# fasciaMainBoard_V0.net
KiCad netlist of a schematic drawn in EAGLE
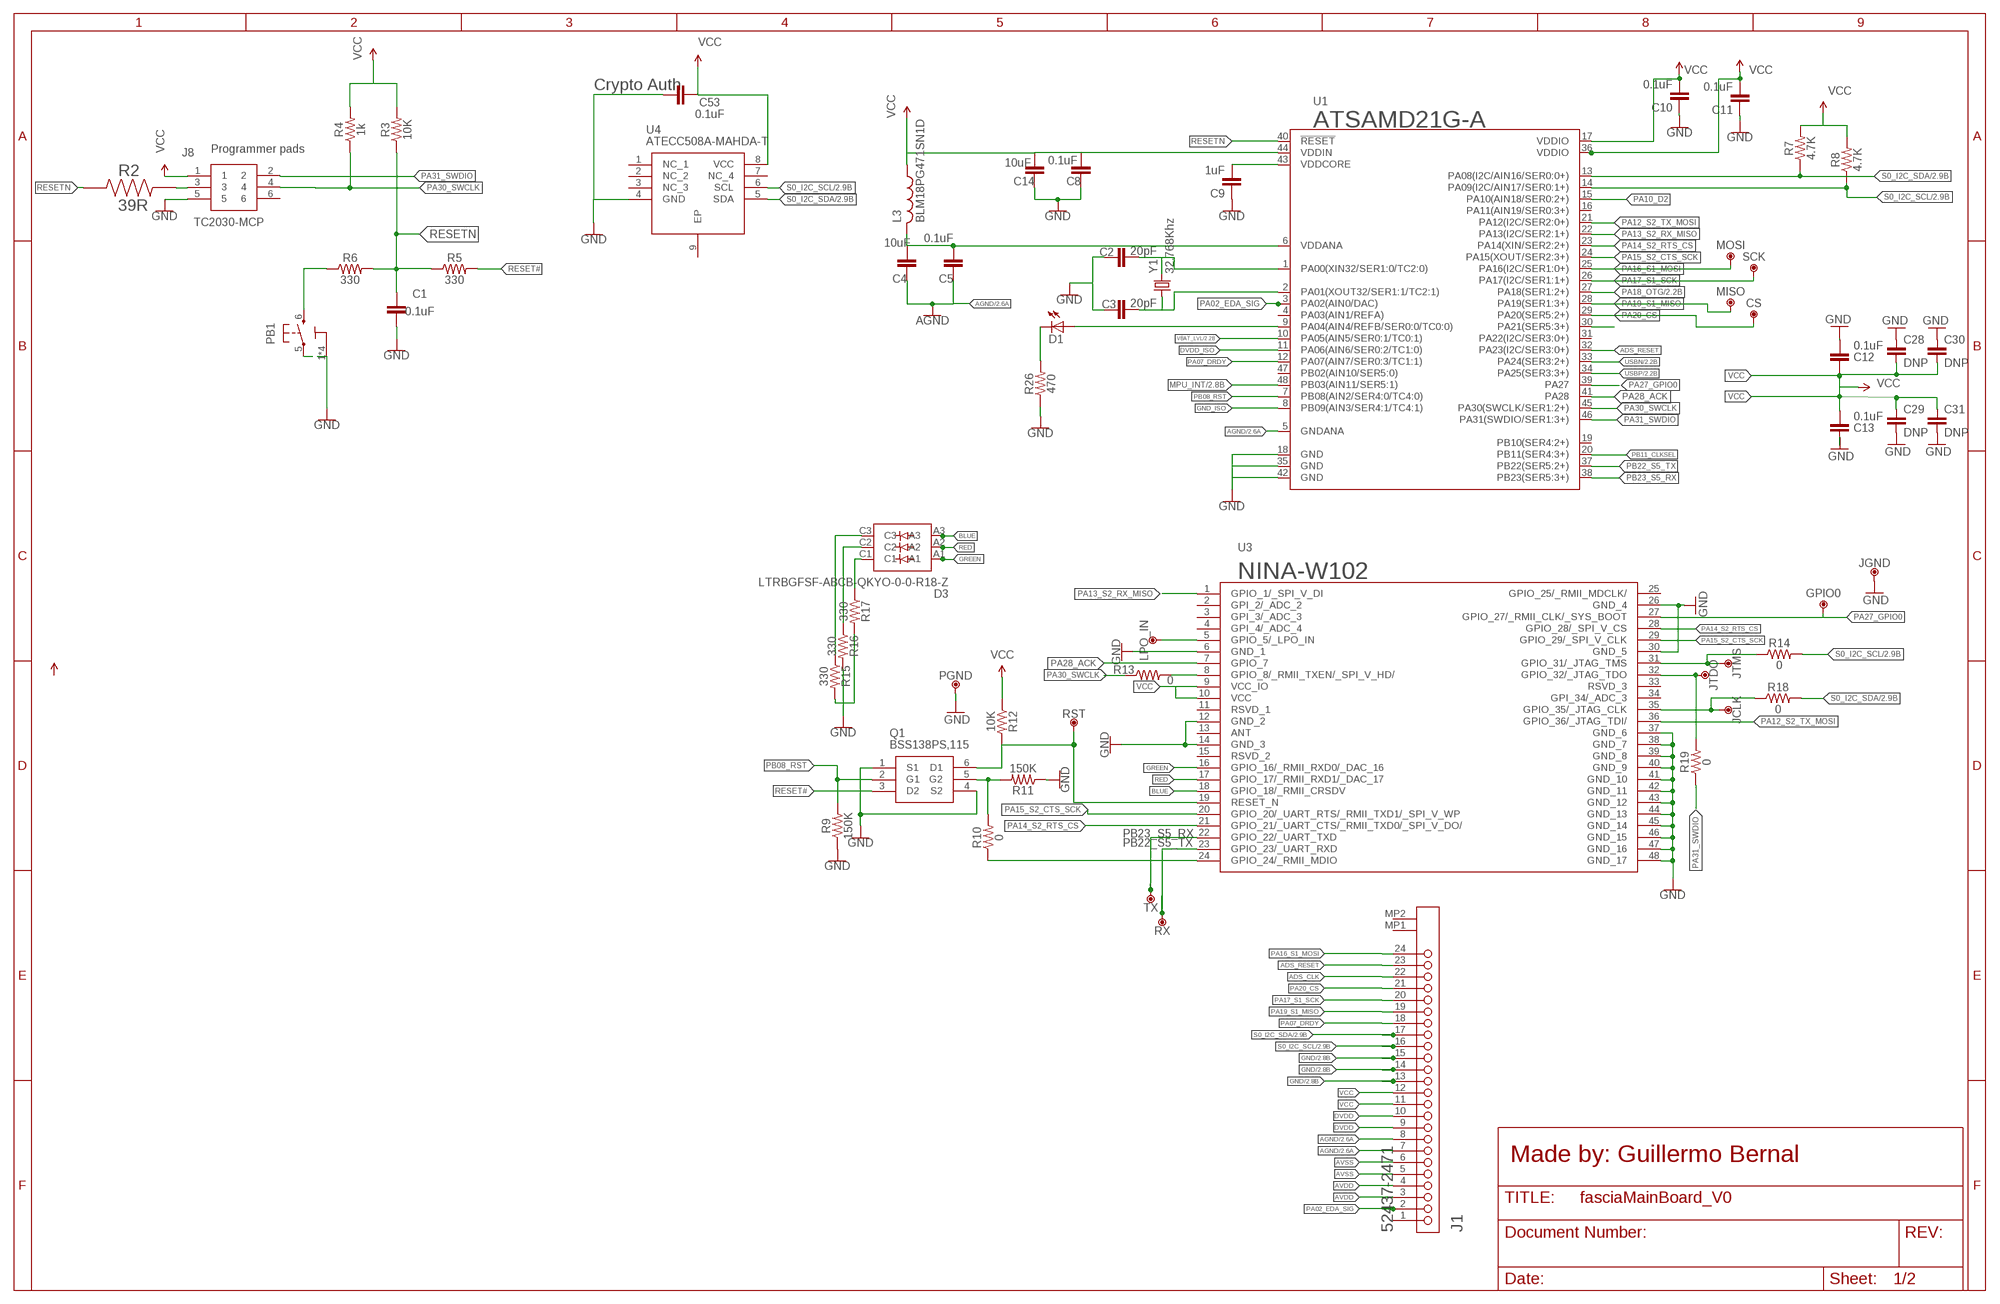
[diagram p0: schematic, sheet 1]
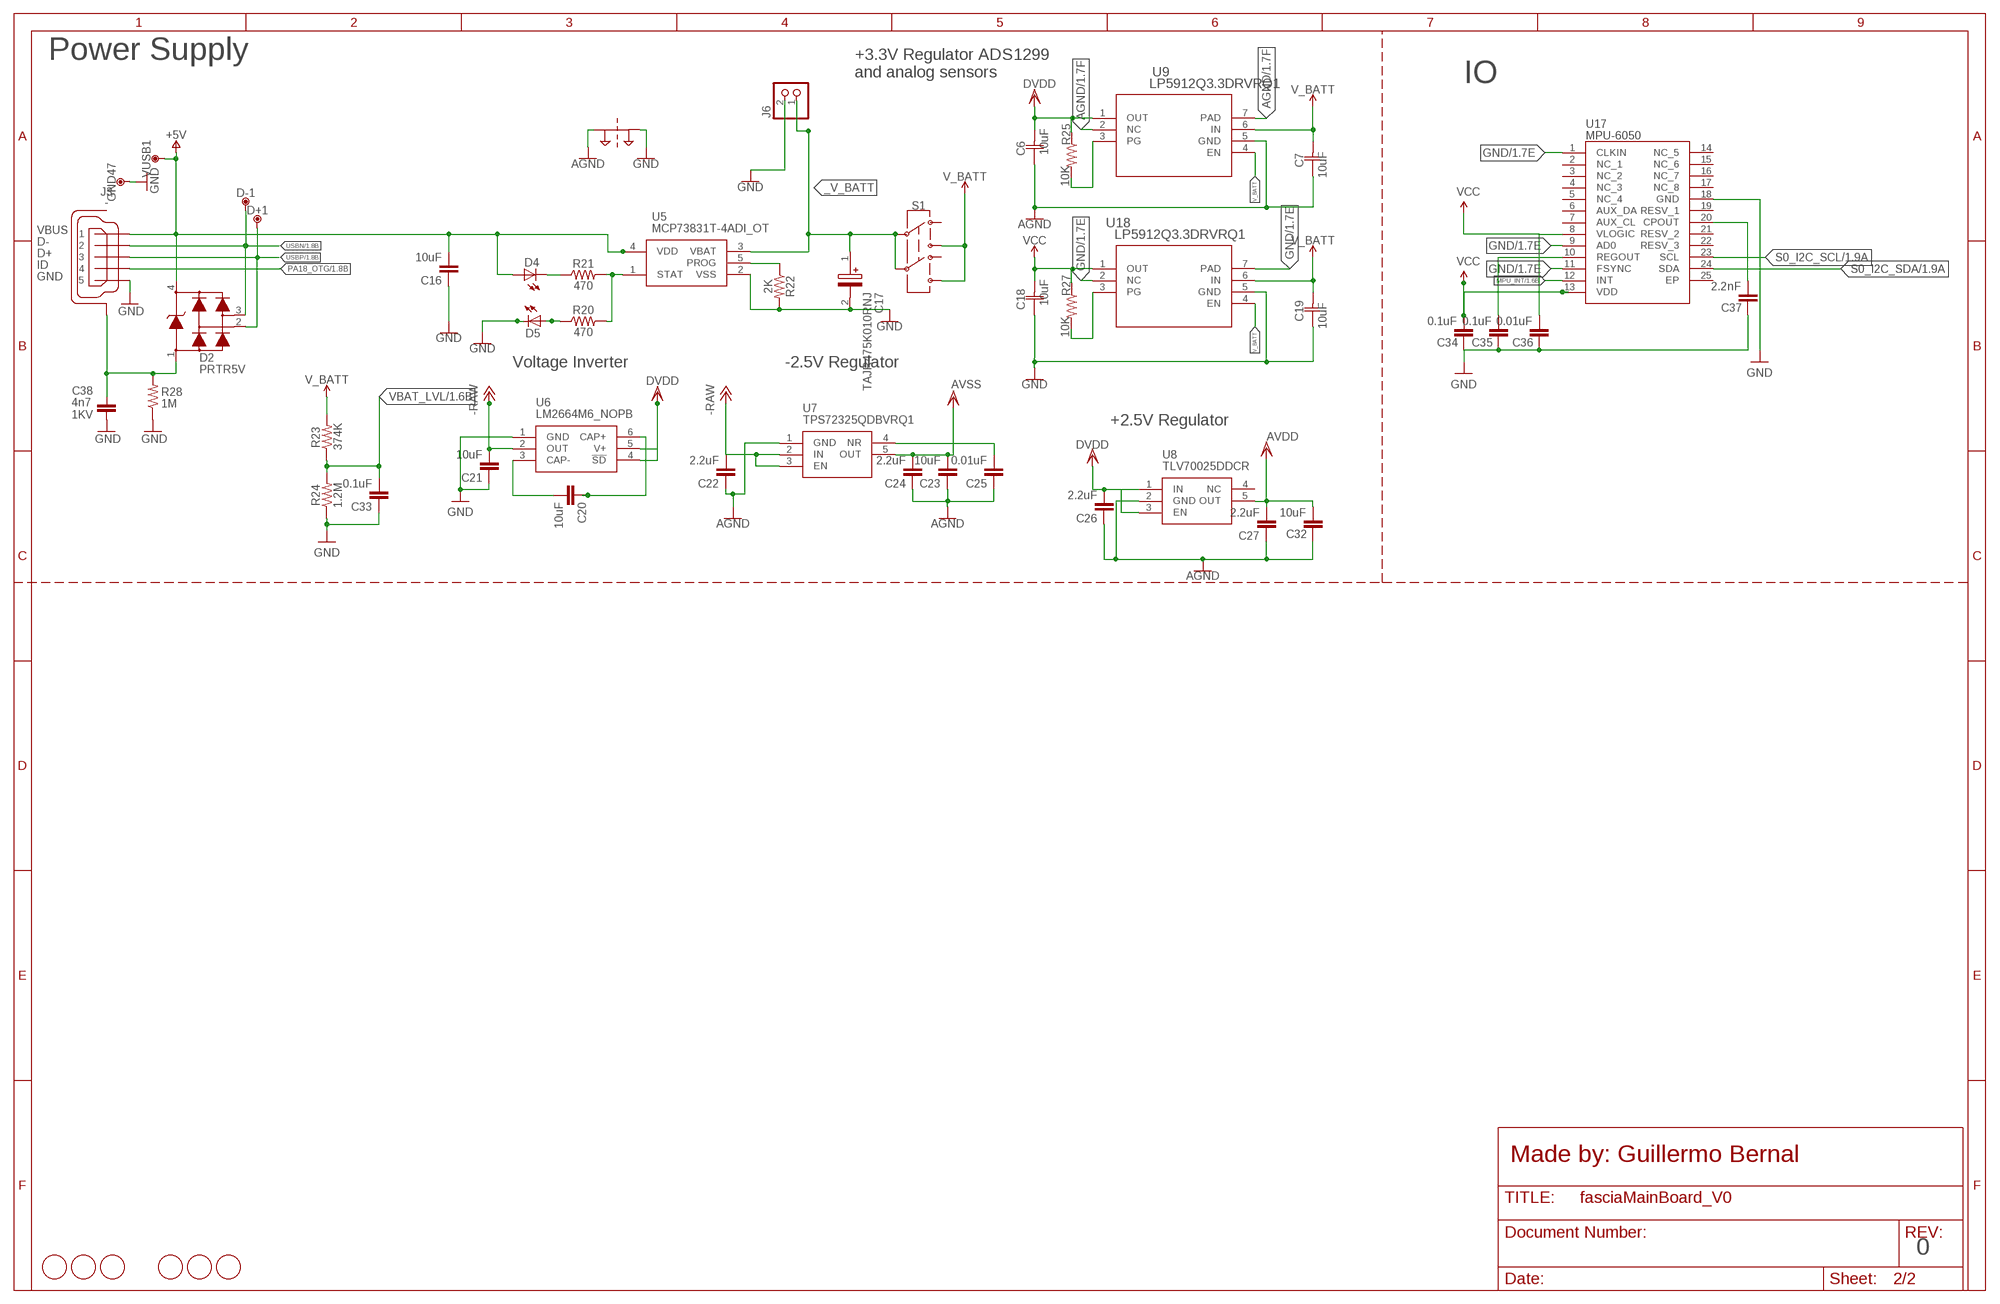
[diagram p1: schematic, sheet 2]

(export (version "E")
  (design (tool "Eeschema 10.0.6"))
  (components
    (comp (ref "C1")
      (value "0.1uF")
      (footprint "eagle-import:0402-TIGHT")
      (libsource (lib "eagle-import") (part "0.1UF-0402T-16V-10%"))
    )
    (comp (ref "C2")
      (value "20pF")
      (footprint "eagle-import:0402-TIGHT")
      (libsource (lib "eagle-import") (part "20PF-0402T-16V-10%"))
    )
    (comp (ref "C3")
      (value "20pF")
      (footprint "eagle-import:0402-TIGHT")
      (libsource (lib "eagle-import") (part "20PF-0402T-16V-10%"))
    )
    (comp (ref "C4")
      (value "10uF")
      (footprint "eagle-import:0603")
      (libsource (lib "eagle-import") (part "SparkFun-Capacitors_510_10UF-0603-6.3V-20%"))
    )
    (comp (ref "C5")
      (value "0.1uF")
      (footprint "eagle-import:0402-TIGHT")
      (libsource (lib "eagle-import") (part "0.1UF-0402T-16V-10%"))
    )
    (comp (ref "C8")
      (value "0.1uF")
      (footprint "eagle-import:0402-TIGHT")
      (libsource (lib "eagle-import") (part "0.1UF-0402T-16V-10%"))
    )
    (comp (ref "C9")
      (value "1uF")
      (footprint "eagle-import:0402-TIGHT")
      (libsource (lib "eagle-import") (part "1UF-0402T-16V-10%"))
    )
    (comp (ref "C10")
      (value "0.1uF")
      (footprint "eagle-import:0402-TIGHT")
      (libsource (lib "eagle-import") (part "0.1UF-0402T-16V-10%"))
    )
    (comp (ref "C11")
      (value "0.1uF")
      (footprint "eagle-import:0402-TIGHT")
      (libsource (lib "eagle-import") (part "0.1UF-0402T-16V-10%"))
    )
    (comp (ref "C12")
      (value "0.1uF")
      (footprint "eagle-import:0402-TIGHT")
      (libsource (lib "eagle-import") (part "0.1UF-0402T-16V-10%"))
    )
    (comp (ref "C13")
      (value "0.1uF")
      (footprint "eagle-import:0402-TIGHT")
      (libsource (lib "eagle-import") (part "0.1UF-0402T-16V-10%"))
    )
    (comp (ref "C14")
      (value "10uF")
      (footprint "eagle-import:0603")
      (libsource (lib "eagle-import") (part "SparkFun-Capacitors_510_10UF-0603-6.3V-20%"))
    )
    (comp (ref "C28")
      (value "DNP")
      (footprint "eagle-import:0402-1005X55N")
      (libsource (lib "eagle-import") (part "C-0402DNP"))
    )
    (comp (ref "C29")
      (value "DNP")
      (footprint "eagle-import:0402-1005X55N")
      (libsource (lib "eagle-import") (part "C-0402DNP"))
    )
    (comp (ref "C30")
      (value "DNP")
      (footprint "eagle-import:0603-1608X90N")
      (libsource (lib "eagle-import") (part "C-0603-DNP"))
    )
    (comp (ref "C31")
      (value "DNP")
      (footprint "eagle-import:0603-1608X90N")
      (libsource (lib "eagle-import") (part "C-0603-DNP"))
    )
    (comp (ref "C53")
      (value "0.1uF")
      (footprint "eagle-import:0402-TIGHT")
      (libsource (lib "eagle-import") (part "0.1UF-0402T-16V-10%"))
    )
    (comp (ref "CS")
      (value "DNP")
      (footprint "eagle-import:TP-0.8MM")
      (libsource (lib "eagle-import") (part "TPTP-0.8MM"))
    )
    (comp (ref "D1")
      (value "LEDCHIPLED_0603")
      (footprint "eagle-import:CHIPLED_0603")
      (libsource (lib "eagle-import") (part "LEDCHIPLED_0603"))
    )
    (comp (ref "D3")
      (value "LTRBGFSF-ABCB-QKYO-0-0-R18-Z")
      (footprint "eagle-import:PLCC-6")
      (libsource (lib "eagle-import") (part "LTRBGFSF-ABCB-QKYO-0-0-R18-Z"))
    )
    (comp (ref "GPIO0")
      (value "DNP")
      (footprint "eagle-import:TP-0.8MM")
      (libsource (lib "eagle-import") (part "TPTP-0.8MM"))
    )
    (comp (ref "J1")
      (value "MOLEX_52437-2471MOLEX_52437-2471_0_0")
      (footprint "eagle-import:MOLEX_52437-2471_0")
      (fields (field (name "MF") "Molex") (field (name "MPN") "52437-2471"))
      (libsource (lib "eagle-import") (part "MOLEX_52437-2471MOLEX_52437-2471_0_0"))
    )
    (comp (ref "J8")
      (value "TC2030-MCP")
      (footprint "eagle-import:TC2030MCP")
      (fields (field (name "MOUSER_PART_NUMBER") "579-TC2030-MCP") (field (name "RS_PART_NUMBER") "8252568"))
      (libsource (lib "eagle-import") (part "TC2030-MCP"))
    )
    (comp (ref "JCLK")
      (value "DNP")
      (footprint "eagle-import:TP-0.8MM")
      (libsource (lib "eagle-import") (part "TPTP-0.8MM"))
    )
    (comp (ref "JGND")
      (value "DNP")
      (footprint "eagle-import:TP-0.8MM")
      (libsource (lib "eagle-import") (part "TPTP-0.8MM"))
    )
    (comp (ref "JTDO")
      (value "DNP")
      (footprint "eagle-import:TP-0.8MM")
      (libsource (lib "eagle-import") (part "TPTP-0.8MM"))
    )
    (comp (ref "JTMS")
      (value "DNP")
      (footprint "eagle-import:TP-0.8MM")
      (libsource (lib "eagle-import") (part "TPTP-0.8MM"))
    )
    (comp (ref "L3")
      (value "BLM18PG471SN1D")
      (footprint "eagle-import:BEADC1608X95N")
      (fields
        (field (name "MOUSER_PART_NUMBER") "81-BLM18PG471SN1D")
        (field (name "RS_PART_NUMBER") "7241425P")
      )
      (libsource (lib "eagle-import") (part "BLM18PG471SN1D"))
    )
    (comp (ref "LPO_IN")
      (value "DNP")
      (footprint "eagle-import:TP-0.8MM")
      (libsource (lib "eagle-import") (part "TPTP-0.8MM"))
    )
    (comp (ref "MISO")
      (value "DNP")
      (footprint "eagle-import:TP-0.8MM")
      (libsource (lib "eagle-import") (part "TPTP-0.8MM"))
    )
    (comp (ref "MOSI")
      (value "DNP")
      (footprint "eagle-import:TP-0.8MM")
      (libsource (lib "eagle-import") (part "TPTP-0.8MM"))
    )
    (comp (ref "PB1")
      (value "PTS820")
      (footprint "eagle-import:C&K_PTS820_NO_HOLES")
      (fields (field (name "MANUFACTURER") "C&K"))
      (libsource (lib "eagle-import") (part "TACTILE1PTS820-NH"))
    )
    (comp (ref "PGND")
      (value "DNP")
      (footprint "eagle-import:TP-0.8MM")
      (libsource (lib "eagle-import") (part "TPTP-0.8MM"))
    )
    (comp (ref "Q1")
      (value "BSS138PS,115")
      (footprint "eagle-import:SOT65P210X110-6N")
      (fields
        (field (name "MOUSER_PART_NUMBER") "771-BSS138PS115")
        (field (name "RS_PART_NUMBER") "7920901P")
      )
      (libsource (lib "eagle-import") (part "BSS138PS,115"))
    )
    (comp (ref "R2")
      (value "39R")
      (footprint "eagle-import:RESC1005X40N")
      (fields (field (name "MF") "Yageo") (field (name "MP") "RC0402FR-0739RL"))
      (libsource (lib "eagle-import") (part "RC0402FR-0739RL"))
    )
    (comp (ref "R3")
      (value "10K")
      (footprint "eagle-import:0402-TIGHT")
      (libsource (lib "eagle-import") (part "10K"))
    )
    (comp (ref "R4")
      (value "1k")
      (footprint "eagle-import:0402-TIGHT")
      (libsource (lib "eagle-import") (part "1K"))
    )
    (comp (ref "R5")
      (value "330")
      (footprint "eagle-import:0402-TIGHT")
      (libsource (lib "eagle-import") (part "330"))
    )
    (comp (ref "R6")
      (value "330")
      (footprint "eagle-import:0402-TIGHT")
      (libsource (lib "eagle-import") (part "330"))
    )
    (comp (ref "R7")
      (value "4.7K")
      (footprint "eagle-import:0402-TIGHT")
      (libsource (lib "eagle-import") (part "4.7K"))
    )
    (comp (ref "R8")
      (value "4.7K")
      (footprint "eagle-import:0402-TIGHT")
      (libsource (lib "eagle-import") (part "4.7K"))
    )
    (comp (ref "R9")
      (value "150K")
      (footprint "eagle-import:0402-TIGHT")
      (libsource (lib "eagle-import") (part "100K"))
    )
    (comp (ref "R10")
      (value "0")
      (footprint "eagle-import:0402-TIGHT")
      (libsource (lib "eagle-import") (part "0"))
    )
    (comp (ref "R11")
      (value "150K")
      (footprint "eagle-import:0402-TIGHT")
      (libsource (lib "eagle-import") (part "100K"))
    )
    (comp (ref "R12")
      (value "10K")
      (footprint "eagle-import:0402-TIGHT")
      (libsource (lib "eagle-import") (part "10K"))
    )
    (comp (ref "R13")
      (value "0")
      (footprint "eagle-import:0402-TIGHT")
      (libsource (lib "eagle-import") (part "0"))
    )
    (comp (ref "R14")
      (value "0")
      (footprint "eagle-import:0402-TIGHT")
      (libsource (lib "eagle-import") (part "0"))
    )
    (comp (ref "R15")
      (value "330")
      (footprint "eagle-import:0402-TIGHT")
      (libsource (lib "eagle-import") (part "330"))
    )
    (comp (ref "R16")
      (value "330")
      (footprint "eagle-import:0402-TIGHT")
      (libsource (lib "eagle-import") (part "330"))
    )
    (comp (ref "R17")
      (value "330")
      (footprint "eagle-import:0402-TIGHT")
      (libsource (lib "eagle-import") (part "330"))
    )
    (comp (ref "R18")
      (value "0")
      (footprint "eagle-import:0402-TIGHT")
      (libsource (lib "eagle-import") (part "0"))
    )
    (comp (ref "R19")
      (value "0")
      (footprint "eagle-import:0402-TIGHT")
      (libsource (lib "eagle-import") (part "0"))
    )
    (comp (ref "R26")
      (value "470")
      (footprint "eagle-import:0402-TIGHT")
      (libsource (lib "eagle-import") (part "470"))
    )
    (comp (ref "RST")
      (value "DNP")
      (footprint "eagle-import:TP-0.8MM")
      (libsource (lib "eagle-import") (part "TPTP-0.8MM"))
    )
    (comp (ref "RX")
      (value "DNP")
      (footprint "eagle-import:TP-0.8MM")
      (libsource (lib "eagle-import") (part "TPTP-0.8MM"))
    )
    (comp (ref "SCK")
      (value "DNP")
      (footprint "eagle-import:TP-0.8MM")
      (libsource (lib "eagle-import") (part "TPTP-0.8MM"))
    )
    (comp (ref "TX")
      (value "DNP")
      (footprint "eagle-import:TP-0.8MM")
      (libsource (lib "eagle-import") (part "TPTP-0.8MM"))
    )
    (comp (ref "U1")
      (value "ATSAMD21G-A")
      (footprint "eagle-import:TQFP-48")
      (libsource (lib "eagle-import") (part "ATSAMD21G-A"))
    )
    (comp (ref "U3")
      (value "NINA-W102")
      (footprint "eagle-import:NINAW102")
      (libsource (lib "eagle-import") (part "NINA-W102"))
    )
    (comp (ref "U4")
      (value "ATECC508A-MAHDA-T")
      (footprint "eagle-import:SON50P300X200X60-9N")
      (fields
        (field (name "MOUSER_PART_NUMBER") "556-ATECC508A-MAHDAT")
        (field (name "RS_PART_NUMBER") "1773144P")
      )
      (libsource (lib "eagle-import") (part "ATECC508A-MAHDA-T"))
    )
    (comp (ref "Y1")
      (value "32.768Khz")
      (footprint "eagle-import:ECX-31B")
      (fields
        (field (name "MANUFACTURER_PART_NUMBER") "ECS-.327-12.5-34B-TR")
        (field (name "MOUSER_PART_NUMBER") "520-327-12.5-34B")
      )
      (libsource (lib "eagle-import") (part "ECS-.327-12.5-34B-TR"))
    )
    (comp (ref "C6")
      (value "10uF")
      (footprint "eagle-import:CAP_CL10-L")
      (fields (field (name "MANUFACTURER_PART_NUMBER") "CL10B106MQ8NRNC"))
      (libsource (lib "eagle-import") (part "CL10B106MQ8NRNCCAP_CL10-L"))
    )
    (comp (ref "C7")
      (value "10uF")
      (footprint "eagle-import:CAP_CL10-L")
      (fields (field (name "MANUFACTURER_PART_NUMBER") "CL10B106MQ8NRNC"))
      (libsource (lib "eagle-import") (part "CL10B106MQ8NRNCCAP_CL10-L"))
    )
    (comp (ref "C16")
      (value "10uF")
      (footprint "eagle-import:0603")
      (libsource (lib "eagle-import") (part "10UF-0603-6.3V-20%"))
    )
    (comp (ref "C17")
      (value "TAJR475K010RNJ")
      (footprint "eagle-import:CAPPM2014X120N")
      (fields
        (field (name "MOUSER_PART_NUMBER") "581-TAJR475K010R")
        (field (name "RS_PART_NUMBER") "1355409P")
      )
      (libsource (lib "eagle-import") (part "TAJR475K010RNJ"))
    )
    (comp (ref "C18")
      (value "10uF")
      (footprint "eagle-import:CAP_CL10-L")
      (fields (field (name "MANUFACTURER_PART_NUMBER") "CL10B106MQ8NRNC"))
      (libsource (lib "eagle-import") (part "CL10B106MQ8NRNCCAP_CL10-L"))
    )
    (comp (ref "C19")
      (value "10uF")
      (footprint "eagle-import:CAP_CL10-L")
      (fields (field (name "MANUFACTURER_PART_NUMBER") "CL10B106MQ8NRNC"))
      (libsource (lib "eagle-import") (part "CL10B106MQ8NRNCCAP_CL10-L"))
    )
    (comp (ref "C20")
      (value "10uF")
      (footprint "eagle-import:0603")
      (libsource (lib "eagle-import") (part "10UF-0603-6.3V-20%"))
    )
    (comp (ref "C21")
      (value "10uF")
      (footprint "eagle-import:0603")
      (libsource (lib "eagle-import") (part "10UF-0603-6.3V-20%"))
    )
    (comp (ref "C22")
      (value "2.2uF")
      (footprint "eagle-import:0402-TIGHT")
      (libsource (lib "eagle-import") (part "2.2UF-0402T-16V-10%"))
    )
    (comp (ref "C23")
      (value "10uF")
      (footprint "eagle-import:0603")
      (libsource (lib "eagle-import") (part "10UF-0603-6.3V-20%"))
    )
    (comp (ref "C24")
      (value "2.2uF")
      (footprint "eagle-import:0402-TIGHT")
      (libsource (lib "eagle-import") (part "2.2UF-0402T-16V-10%"))
    )
    (comp (ref "C25")
      (value "0.01uF")
      (footprint "eagle-import:0402-TIGHT")
      (libsource (lib "eagle-import") (part "0.01UF-0402T-16V-10%"))
    )
    (comp (ref "C26")
      (value "2.2uF")
      (footprint "eagle-import:0402-TIGHT")
      (libsource (lib "eagle-import") (part "2.2UF-0402T-16V-10%"))
    )
    (comp (ref "C27")
      (value "2.2uF")
      (footprint "eagle-import:0402-TIGHT")
      (libsource (lib "eagle-import") (part "2.2UF-0402T-16V-10%"))
    )
    (comp (ref "C32")
      (value "10uF")
      (footprint "eagle-import:0603")
      (libsource (lib "eagle-import") (part "10UF-0603-6.3V-20%"))
    )
    (comp (ref "C33")
      (value "0.1uF")
      (footprint "eagle-import:0402-TIGHT")
      (libsource (lib "eagle-import") (part "0.1UF-0402T-16V-10%"))
    )
    (comp (ref "C34")
      (value "0.1uF")
      (footprint "eagle-import:0402-TIGHT")
      (libsource (lib "eagle-import") (part "0.1UF-0402T-16V-10%"))
    )
    (comp (ref "C35")
      (value "0.1uF")
      (footprint "eagle-import:0402-TIGHT")
      (libsource (lib "eagle-import") (part "0.1UF-0402T-16V-10%"))
    )
    (comp (ref "C36")
      (value "0.01uF")
      (footprint "eagle-import:0402-TIGHT")
      (libsource (lib "eagle-import") (part "0.01UF-0402T-16V-10%"))
    )
    (comp (ref "C37")
      (value "2.2nF")
      (footprint "eagle-import:0402-TIGHT")
      (libsource (lib "eagle-import") (part "2.2NF-0402T-16V-10%"))
    )
    (comp (ref "C38")
      (value "4n7")
      (footprint "eagle-import:0805-R2013X50N")
      (fields (field (name "MANUFACTURER") "Kemet") (field (name "VOLTAGE") "1KV"))
      (libsource (lib "eagle-import") (part "C-08054.7NF"))
    )
    (comp (ref "D+1")
      (value "DNP")
      (footprint "eagle-import:TP-1.00MM")
      (libsource (lib "eagle-import") (part "TPTP-1.00MM"))
    )
    (comp (ref "D-1")
      (value "DNP")
      (footprint "eagle-import:TP-1.00MM")
      (libsource (lib "eagle-import") (part "TPTP-1.00MM"))
    )
    (comp (ref "D2")
      (value "PRTR5V")
      (footprint "eagle-import:SOT190P230X110-4N")
      (fields (field (name "MANUFACTURER") "NXP"))
      (libsource (lib "eagle-import") (part "PRTR5V0U2X,215"))
    )
    (comp (ref "D4")
      (value "LEDCHIPLED_0603")
      (footprint "eagle-import:CHIPLED_0603")
      (libsource (lib "eagle-import") (part "LEDCHIPLED_0603"))
    )
    (comp (ref "D5")
      (value "LEDCHIPLED_0603")
      (footprint "eagle-import:CHIPLED_0603")
      (libsource (lib "eagle-import") (part "LEDCHIPLED_0603"))
    )
    (comp (ref "FD1")
      (value "DNP")
      (footprint "eagle-import:FD-1-1.5")
      (libsource (lib "eagle-import") (part "FIDUCIAL-1.5MM"))
    )
    (comp (ref "FD2")
      (value "DNP")
      (footprint "eagle-import:FD-1-1.5")
      (libsource (lib "eagle-import") (part "FIDUCIAL-1.5MM"))
    )
    (comp (ref "FD3")
      (value "DNP")
      (footprint "eagle-import:FD-1-1.5")
      (libsource (lib "eagle-import") (part "FIDUCIAL-1.5MM"))
    )
    (comp (ref "FD4")
      (value "DNP")
      (footprint "eagle-import:FD-1-1.5")
      (libsource (lib "eagle-import") (part "FIDUCIAL-1.5MM"))
    )
    (comp (ref "FD5")
      (value "DNP")
      (footprint "eagle-import:FD-1-1.5")
      (libsource (lib "eagle-import") (part "FIDUCIAL-1.5MM"))
    )
    (comp (ref "FD6")
      (value "DNP")
      (footprint "eagle-import:FD-1-1.5")
      (libsource (lib "eagle-import") (part "FIDUCIAL-1.5MM"))
    )
    (comp (ref "GND47")
      (value "DNP")
      (footprint "eagle-import:TP-1.00MM")
      (libsource (lib "eagle-import") (part "TPTP-1.00MM"))
    )
    (comp (ref "J3")
      (value "-")
      (footprint "eagle-import:ZX62-AB-5PA")
      (fields (field (name "MANUFACTURER") "Hirose"))
      (libsource (lib "eagle-import") (part "USB-MICRO"))
    )
    (comp (ref "J6")
      (value "JST_2PIN-SMT-RA")
      (footprint "eagle-import:JST-PH-2-SMT-RA")
      (libsource (lib "eagle-import") (part "JST_2PIN-SMT-RA"))
    )
    (comp (ref "R20")
      (value "470")
      (footprint "eagle-import:0402-TIGHT")
      (libsource (lib "eagle-import") (part "470"))
    )
    (comp (ref "R21")
      (value "470")
      (footprint "eagle-import:0402-TIGHT")
      (libsource (lib "eagle-import") (part "470"))
    )
    (comp (ref "R22")
      (value "2K")
      (footprint "eagle-import:0402-TIGHT")
      (libsource (lib "eagle-import") (part "2K"))
    )
    (comp (ref "R23")
      (value "374K")
      (footprint "eagle-import:0402-TIGHT")
      (libsource (lib "eagle-import") (part "374K"))
    )
    (comp (ref "R24")
      (value "1.2M")
      (footprint "eagle-import:0402")
      (libsource (lib "eagle-import") (part "1.2M-0402-1/10W-1%"))
    )
    (comp (ref "R25")
      (value "10K")
      (footprint "eagle-import:0402-TIGHT")
      (libsource (lib "eagle-import") (part "10K"))
    )
    (comp (ref "R27")
      (value "10K")
      (footprint "eagle-import:0402-TIGHT")
      (libsource (lib "eagle-import") (part "10K"))
    )
    (comp (ref "R28")
      (value "1M")
      (footprint "eagle-import:0402-TIGHT")
      (libsource (lib "eagle-import") (part "1M"))
    )
    (comp (ref "S1")
      (value "SWITCH-DPDT-SMD-AYZ0202")
      (footprint "eagle-import:SWITCH_DPDT_SMD_AYZ0202")
      (libsource (lib "eagle-import") (part "SWITCH-DPDT-SMD-AYZ0202"))
    )
    (comp (ref "SUPPLY1")
      (value "2PT_GND_TIE")
      (footprint "eagle-import:2PT_GND_TIE")
      (libsource (lib "eagle-import") (part "2PT_GND_TIE"))
    )
    (comp (ref "U5")
      (value "MCP73831T-4ADI_OT")
      (footprint "eagle-import:SOT95P270X145-5N")
      (fields
        (field (name "MANUFACTURER_PART_NUMBER") "MCP73831T-4ADI/OT")
        (field (name "MOUSER_PART_NUMBER") "579-MCP73831T4ADIOT")
      )
      (libsource (lib "eagle-import") (part "MCP73831T-4ADI_OT"))
    )
    (comp (ref "U6")
      (value "LM2664M6_NOPB")
      (footprint "eagle-import:SOT95P280X145-6N")
      (fields
        (field (name "MANUFACTURER_PART_NUMBER") "LM2664M6/NOPB")
        (field (name "MOUSER_PART_NUMBER") "926-LM2664M6/NOPB")
        (field (name "RS_PART_NUMBER") "5358792P")
      )
      (libsource (lib "eagle-import") (part "LM2664M6_NOPB"))
    )
    (comp (ref "U7")
      (value "TPS72325QDBVRQ1")
      (footprint "eagle-import:SOT96P230X110-5N")
      (libsource (lib "eagle-import") (part "TPS72325QDBVRQ1"))
    )
    (comp (ref "U8")
      (value "TLV70025DDCR")
      (footprint "eagle-import:SOT95P280X110-5N")
      (fields (field (name "MOUSER_PART_NUMBER") "595-TLV70025DDCR"))
      (libsource (lib "eagle-import") (part "TLV70025DDCR"))
    )
    (comp (ref "U9")
      (value "LP5912Q3.3DRVRQ1")
      (footprint "eagle-import:DRV0006A")
      (libsource (lib "eagle-import") (part "LP5912Q3.3DRVRQ1"))
    )
    (comp (ref "U17")
      (value "MPU-6050")
      (footprint "eagle-import:MPU6050")
      (fields (field (name "MOUSER_PART_NUMBER") "410-MPU-6050"))
      (libsource (lib "eagle-import") (part "MPU-6050"))
    )
    (comp (ref "U18")
      (value "LP5912Q3.3DRVRQ1")
      (footprint "eagle-import:DRV0006A")
      (libsource (lib "eagle-import") (part "LP5912Q3.3DRVRQ1"))
    )
    (comp (ref "VUSB1")
      (value "DNP")
      (footprint "eagle-import:TP-1.00MM")
      (libsource (lib "eagle-import") (part "TPTP-1.00MM"))
    )
  )
  (nets
    (net (code "1") (name "+5V") (class "Default")
      (node (ref "C16") (pin "2") (pinfunction "2_2") (pintype "passive"))
      (node (ref "D2") (pin "4") (pinfunction "4_4") (pintype "passive"))
      (node (ref "D4") (pin "A") (pinfunction "A_A") (pintype "passive"))
      (node (ref "J3") (pin "1") (pinfunction "1_1") (pintype "passive"))
      (node (ref "U5") (pin "4") (pinfunction "VDD_4") (pintype "bidirectional"))
      (node (ref "VUSB1") (pin "X") (pinfunction "P$1_X") (pintype "passive"))
    )
    (net (code "2") (name "-RAW") (class "Default")
      (node (ref "C21") (pin "2") (pinfunction "2_2") (pintype "passive"))
      (node (ref "C22") (pin "2") (pinfunction "2_2") (pintype "passive"))
      (node (ref "U6") (pin "2") (pinfunction "OUT_2") (pintype "output"))
      (node (ref "U7") (pin "2") (pinfunction "IN_2") (pintype "power_in"))
      (node (ref "U7") (pin "3") (pinfunction "EN_3") (pintype "bidirectional"))
    )
    (net (code "3") (name "ADS_CLK") (class "Default")
      (node (ref "J1") (pin "22") (pinfunction "22_22") (pintype "passive"))
    )
    (net (code "4") (name "ADS_RESET") (class "Default")
      (node (ref "J1") (pin "23") (pinfunction "23_23") (pintype "passive"))
      (node (ref "U1") (pin "32") (pinfunction "PA23(I2C/SER3:0+)_32") (pintype "bidirectional"))
    )
    (net (code "5") (name "AGND") (class "Default")
      (node (ref "C22") (pin "1") (pinfunction "1_1") (pintype "passive"))
      (node (ref "C23") (pin "1") (pinfunction "1_1") (pintype "passive"))
      (node (ref "C24") (pin "1") (pinfunction "1_1") (pintype "passive"))
      (node (ref "C25") (pin "1") (pinfunction "1_1") (pintype "passive"))
      (node (ref "C26") (pin "1") (pinfunction "1_1") (pintype "passive"))
      (node (ref "C27") (pin "1") (pinfunction "1_1") (pintype "passive"))
      (node (ref "C32") (pin "1") (pinfunction "1_1") (pintype "passive"))
      (node (ref "C4") (pin "1") (pinfunction "1_1") (pintype "passive"))
      (node (ref "C5") (pin "1") (pinfunction "1_1") (pintype "passive"))
      (node (ref "C6") (pin "1") (pinfunction "1_1") (pintype "passive"))
      (node (ref "C7") (pin "1") (pinfunction "1_1") (pintype "passive"))
      (node (ref "J1") (pin "7") (pinfunction "7_7") (pintype "passive"))
      (node (ref "J1") (pin "8") (pinfunction "8_8") (pintype "passive"))
      (node (ref "SUPPLY1") (pin "P$1") (pinfunction "P$1_P$1") (pintype "bidirectional"))
      (node (ref "U1") (pin "5") (pinfunction "GNDANA_5") (pintype "bidirectional"))
      (node (ref "U7") (pin "1") (pinfunction "GND_1") (pintype "power_in"))
      (node (ref "U8") (pin "2") (pinfunction "GND_2") (pintype "bidirectional"))
      (node (ref "U9") (pin "2") (pinfunction "NC_2") (pintype "passive"))
      (node (ref "U9") (pin "5") (pinfunction "GND_5") (pintype "power_in"))
      (node (ref "U9") (pin "7") (pinfunction "PAD_7") (pintype "power_in"))
    )
    (net (code "6") (name "AVDD") (class "Default")
      (node (ref "C27") (pin "2") (pinfunction "2_2") (pintype "passive"))
      (node (ref "C32") (pin "2") (pinfunction "2_2") (pintype "passive"))
      (node (ref "J1") (pin "3") (pinfunction "3_3") (pintype "passive"))
      (node (ref "J1") (pin "4") (pinfunction "4_4") (pintype "passive"))
      (node (ref "U8") (pin "5") (pinfunction "OUT_5") (pintype "bidirectional"))
    )
    (net (code "7") (name "AVSS") (class "Default")
      (node (ref "C23") (pin "2") (pinfunction "2_2") (pintype "passive"))
      (node (ref "C24") (pin "2") (pinfunction "2_2") (pintype "passive"))
      (node (ref "J1") (pin "5") (pinfunction "5_5") (pintype "passive"))
      (node (ref "J1") (pin "6") (pinfunction "6_6") (pintype "passive"))
      (node (ref "U7") (pin "5") (pinfunction "OUT_5") (pintype "power_in"))
    )
    (net (code "8") (name "BLUE") (class "Default")
      (node (ref "D3") (pin "A3") (pinfunction "A3_A3") (pintype "bidirectional"))
      (node (ref "U3") (pin "18") (pinfunction "GPIO_18/_RMII_CRSDV_18") (pintype "bidirectional"))
    )
    (net (code "9") (name "DVDD") (class "Default")
      (node (ref "C26") (pin "2") (pinfunction "2_2") (pintype "passive"))
      (node (ref "C6") (pin "2") (pinfunction "2_2") (pintype "passive"))
      (node (ref "J1") (pin "10") (pinfunction "10_10") (pintype "passive"))
      (node (ref "J1") (pin "9") (pinfunction "9_9") (pintype "passive"))
      (node (ref "R25") (pin "1") (pinfunction "1_1") (pintype "passive"))
      (node (ref "U6") (pin "4") (pinfunction "~{SD}_4") (pintype "input"))
      (node (ref "U6") (pin "5") (pinfunction "V+_5") (pintype "power_in"))
      (node (ref "U8") (pin "1") (pinfunction "IN_1") (pintype "bidirectional"))
      (node (ref "U8") (pin "3") (pinfunction "EN_3") (pintype "bidirectional"))
      (node (ref "U9") (pin "1") (pinfunction "OUT_1") (pintype "power_in"))
    )
    (net (code "10") (name "DVDD_ISO") (class "Default")
      (node (ref "U1") (pin "11") (pinfunction "PA06(AIN6/SER0:2/TC1:0)_11") (pintype "bidirectional"))
    )
    (net (code "11") (name "GND") (class "Default")
      (node (ref "C1") (pin "2") (pinfunction "2_2") (pintype "passive"))
      (node (ref "C10") (pin "1") (pinfunction "1_1") (pintype "passive"))
      (node (ref "C11") (pin "1") (pinfunction "1_1") (pintype "passive"))
      (node (ref "C12") (pin "2") (pinfunction "2_2") (pintype "passive"))
      (node (ref "C13") (pin "1") (pinfunction "1_1") (pintype "passive"))
      (node (ref "C14") (pin "1") (pinfunction "1_1") (pintype "passive"))
      (node (ref "C16") (pin "1") (pinfunction "1_1") (pintype "passive"))
      (node (ref "C17") (pin "2") (pinfunction "-_2") (pintype "bidirectional"))
      (node (ref "C18") (pin "1") (pinfunction "1_1") (pintype "passive"))
      (node (ref "C19") (pin "1") (pinfunction "1_1") (pintype "passive"))
      (node (ref "C2") (pin "1") (pinfunction "1_1") (pintype "passive"))
      (node (ref "C21") (pin "1") (pinfunction "1_1") (pintype "passive"))
      (node (ref "C28") (pin "1") (pinfunction "1_1") (pintype "passive"))
      (node (ref "C29") (pin "2") (pinfunction "2_2") (pintype "passive"))
      (node (ref "C3") (pin "1") (pinfunction "1_1") (pintype "passive"))
      (node (ref "C30") (pin "1") (pinfunction "1_1") (pintype "passive"))
      (node (ref "C31") (pin "2") (pinfunction "2_2") (pintype "passive"))
      (node (ref "C33") (pin "1") (pinfunction "1_1") (pintype "passive"))
      (node (ref "C34") (pin "1") (pinfunction "1_1") (pintype "passive"))
      (node (ref "C35") (pin "1") (pinfunction "1_1") (pintype "passive"))
      (node (ref "C36") (pin "1") (pinfunction "1_1") (pintype "passive"))
      (node (ref "C37") (pin "1") (pinfunction "1_1") (pintype "passive"))
      (node (ref "C38") (pin "2") (pinfunction "2_2") (pintype "passive"))
      (node (ref "C53") (pin "2") (pinfunction "2_2") (pintype "passive"))
      (node (ref "C8") (pin "1") (pinfunction "1_1") (pintype "passive"))
      (node (ref "C9") (pin "1") (pinfunction "1_1") (pintype "passive"))
      (node (ref "D5") (pin "C") (pinfunction "C_C") (pintype "passive"))
      (node (ref "GND47") (pin "X") (pinfunction "P$1_X") (pintype "passive"))
      (node (ref "J1") (pin "13") (pinfunction "13_13") (pintype "passive"))
      (node (ref "J1") (pin "14") (pinfunction "14_14") (pintype "passive"))
      (node (ref "J1") (pin "15") (pinfunction "15_15") (pintype "passive"))
      (node (ref "J3") (pin "5") (pinfunction "5_5") (pintype "passive"))
      (node (ref "J6") (pin "2") (pinfunction "1_2") (pintype "passive"))
      (node (ref "J8") (pin "5") (pinfunction "5_5") (pintype "bidirectional"))
      (node (ref "JGND") (pin "X") (pinfunction "P$1_X") (pintype "passive"))
      (node (ref "PB1") (pin "1") (pinfunction "3_1") (pintype "power_in"))
      (node (ref "PB1") (pin "2") (pinfunction "3_2") (pintype "power_in"))
      (node (ref "PB1") (pin "3") (pinfunction "3_3") (pintype "power_in"))
      (node (ref "PB1") (pin "4") (pinfunction "3_4") (pintype "power_in"))
      (node (ref "PB1") (pin "5") (pinfunction "1_5") (pintype "passive"))
      (node (ref "PGND") (pin "X") (pinfunction "P$1_X") (pintype "passive"))
      (node (ref "Q1") (pin "1") (pinfunction "S1_1") (pintype "bidirectional"))
      (node (ref "Q1") (pin "4") (pinfunction "S2_4") (pintype "bidirectional"))
      (node (ref "R11") (pin "1") (pinfunction "1_1") (pintype "passive"))
      (node (ref "R15") (pin "2") (pinfunction "2_2") (pintype "passive"))
      (node (ref "R16") (pin "2") (pinfunction "2_2") (pintype "passive"))
      (node (ref "R17") (pin "2") (pinfunction "2_2") (pintype "passive"))
      (node (ref "R22") (pin "2") (pinfunction "2_2") (pintype "passive"))
      (node (ref "R24") (pin "1") (pinfunction "1_1") (pintype "passive"))
      (node (ref "R26") (pin "1") (pinfunction "1_1") (pintype "passive"))
      (node (ref "R28") (pin "1") (pinfunction "1_1") (pintype "passive"))
      (node (ref "R9") (pin "1") (pinfunction "1_1") (pintype "passive"))
      (node (ref "SUPPLY1") (pin "P$2") (pinfunction "P$2_P$2") (pintype "bidirectional"))
      (node (ref "U1") (pin "18") (pinfunction "GND_18") (pintype "bidirectional"))
      (node (ref "U1") (pin "35") (pinfunction "GND_35") (pintype "bidirectional"))
      (node (ref "U1") (pin "42") (pinfunction "GND_42") (pintype "bidirectional"))
      (node (ref "U17") (pin "1") (pinfunction "CLKIN_1") (pintype "bidirectional"))
      (node (ref "U17") (pin "11") (pinfunction "FSYNC_11") (pintype "bidirectional"))
      (node (ref "U17") (pin "18") (pinfunction "GND_18") (pintype "bidirectional"))
      (node (ref "U17") (pin "9") (pinfunction "AD0_9") (pintype "bidirectional"))
      (node (ref "U18") (pin "2") (pinfunction "NC_2") (pintype "passive"))
      (node (ref "U18") (pin "5") (pinfunction "GND_5") (pintype "power_in"))
      (node (ref "U18") (pin "7") (pinfunction "PAD_7") (pintype "power_in"))
      (node (ref "U3") (pin "12") (pinfunction "GND_2_12") (pintype "bidirectional"))
      (node (ref "U3") (pin "14") (pinfunction "GND_3_14") (pintype "bidirectional"))
      (node (ref "U3") (pin "26") (pinfunction "GND_4_26") (pintype "bidirectional"))
      (node (ref "U3") (pin "30") (pinfunction "GND_5_30") (pintype "bidirectional"))
      (node (ref "U3") (pin "37") (pinfunction "GND_6_37") (pintype "bidirectional"))
      (node (ref "U3") (pin "38") (pinfunction "GND_7_38") (pintype "bidirectional"))
      (node (ref "U3") (pin "39") (pinfunction "GND_8_39") (pintype "bidirectional"))
      (node (ref "U3") (pin "40") (pinfunction "GND_9_40") (pintype "bidirectional"))
      (node (ref "U3") (pin "41") (pinfunction "GND_10_41") (pintype "bidirectional"))
      (node (ref "U3") (pin "42") (pinfunction "GND_11_42") (pintype "bidirectional"))
      (node (ref "U3") (pin "43") (pinfunction "GND_12_43") (pintype "bidirectional"))
      (node (ref "U3") (pin "44") (pinfunction "GND_13_44") (pintype "bidirectional"))
      (node (ref "U3") (pin "45") (pinfunction "GND_14_45") (pintype "bidirectional"))
      (node (ref "U3") (pin "46") (pinfunction "GND_15_46") (pintype "bidirectional"))
      (node (ref "U3") (pin "47") (pinfunction "GND_16_47") (pintype "bidirectional"))
      (node (ref "U3") (pin "48") (pinfunction "GND_17_48") (pintype "bidirectional"))
      (node (ref "U3") (pin "6") (pinfunction "GND_1_6") (pintype "bidirectional"))
      (node (ref "U4") (pin "4") (pinfunction "GND_4") (pintype "bidirectional"))
      (node (ref "U5") (pin "2") (pinfunction "VSS_2") (pintype "bidirectional"))
      (node (ref "U6") (pin "1") (pinfunction "GND_1") (pintype "power_in"))
    )
    (net (code "12") (name "GND_ISO") (class "Default")
      (node (ref "U1") (pin "8") (pinfunction "PB09(AIN3/SER4:1/TC4:1)_8") (pintype "bidirectional"))
    )
    (net (code "13") (name "GREEN") (class "Default")
      (node (ref "D3") (pin "A1") (pinfunction "A1_A1") (pintype "bidirectional"))
      (node (ref "U3") (pin "16") (pinfunction "GPIO_16/_RMII_RXD0/_DAC_16_16") (pintype "bidirectional"))
    )
    (net (code "14") (name "MPU_INT") (class "Default")
      (node (ref "U1") (pin "48") (pinfunction "PB03(AIN11/SER5:1)_48") (pintype "bidirectional"))
      (node (ref "U17") (pin "12") (pinfunction "INT_12") (pintype "bidirectional"))
    )
    (net (code "15") (name "Net-(C38-Pad1)") (class "Default")
      (node (ref "C38") (pin "1") (pinfunction "1_1") (pintype "passive"))
      (node (ref "D2") (pin "1") (pinfunction "1_1") (pintype "passive"))
      (node (ref "J3") (pin "10") (pinfunction "SH_10") (pintype "passive"))
      (node (ref "J3") (pin "11") (pinfunction "SH_11") (pintype "passive"))
      (node (ref "J3") (pin "6") (pinfunction "SH_6") (pintype "passive"))
      (node (ref "J3") (pin "7") (pinfunction "SH_7") (pintype "passive"))
      (node (ref "J3") (pin "8") (pinfunction "SH_8") (pintype "passive"))
      (node (ref "J3") (pin "9") (pinfunction "SH_9") (pintype "passive"))
      (node (ref "R28") (pin "2") (pinfunction "2_2") (pintype "passive"))
    )
    (net (code "16") (name "Net-(D1-PadC)") (class "Default")
      (node (ref "D1") (pin "C") (pinfunction "C_C") (pintype "passive"))
      (node (ref "R26") (pin "2") (pinfunction "2_2") (pintype "passive"))
    )
    (net (code "17") (name "Net-(D3-PadC1)") (class "Default")
      (node (ref "D3") (pin "C1") (pinfunction "C1_C1") (pintype "bidirectional"))
      (node (ref "R17") (pin "1") (pinfunction "1_1") (pintype "passive"))
    )
    (net (code "18") (name "Net-(D3-PadC2)") (class "Default")
      (node (ref "D3") (pin "C2") (pinfunction "C2_C2") (pintype "bidirectional"))
      (node (ref "R16") (pin "1") (pinfunction "1_1") (pintype "passive"))
    )
    (net (code "19") (name "Net-(D3-PadC3)") (class "Default")
      (node (ref "D3") (pin "C3") (pinfunction "C3_C3") (pintype "bidirectional"))
      (node (ref "R15") (pin "1") (pinfunction "1_1") (pintype "passive"))
    )
    (net (code "20") (name "Net-(D4-PadC)") (class "Default")
      (node (ref "D4") (pin "C") (pinfunction "C_C") (pintype "passive"))
      (node (ref "R21") (pin "1") (pinfunction "1_1") (pintype "passive"))
    )
    (net (code "21") (name "Net-(D5-PadA)") (class "Default")
      (node (ref "D5") (pin "A") (pinfunction "A_A") (pintype "passive"))
      (node (ref "R20") (pin "1") (pinfunction "1_1") (pintype "passive"))
    )
    (net (code "22") (name "Net-(J8-Pad3)") (class "Default")
      (node (ref "J8") (pin "3") (pinfunction "3_3") (pintype "bidirectional"))
      (node (ref "R2") (pin "2") (pinfunction "2_2") (pintype "passive"))
    )
    (net (code "23") (name "Net-(JCLK-P$1)") (class "Default")
      (node (ref "JCLK") (pin "X") (pinfunction "P$1_X") (pintype "passive"))
      (node (ref "R18") (pin "1") (pinfunction "1_1") (pintype "passive"))
      (node (ref "U3") (pin "35") (pinfunction "GPIO_35/_JTAG_CLK_35") (pintype "bidirectional"))
    )
    (net (code "24") (name "Net-(JTDO-P$1)") (class "Default")
      (node (ref "JTDO") (pin "X") (pinfunction "P$1_X") (pintype "passive"))
      (node (ref "R19") (pin "2") (pinfunction "2_2") (pintype "passive"))
      (node (ref "U3") (pin "32") (pinfunction "GPIO_32/_JTAG_TDO_32") (pintype "bidirectional"))
    )
    (net (code "25") (name "Net-(JTMS-P$1)") (class "Default")
      (node (ref "JTMS") (pin "X") (pinfunction "P$1_X") (pintype "passive"))
      (node (ref "R14") (pin "1") (pinfunction "1_1") (pintype "passive"))
      (node (ref "U3") (pin "31") (pinfunction "GPIO_31/_JTAG_TMS_31") (pintype "bidirectional"))
    )
    (net (code "26") (name "Net-(LPO_IN-P$1)") (class "Default")
      (node (ref "LPO_IN") (pin "X") (pinfunction "P$1_X") (pintype "passive"))
      (node (ref "U3") (pin "5") (pinfunction "GPIO_5/_LPO_IN_5") (pintype "bidirectional"))
    )
    (net (code "27") (name "Net-(PB1-2)") (class "Default")
      (node (ref "PB1") (pin "6") (pinfunction "2_6") (pintype "passive"))
      (node (ref "R6") (pin "1") (pinfunction "1_1") (pintype "passive"))
    )
    (net (code "28") (name "Net-(Q1-D1)") (class "Default")
      (node (ref "Q1") (pin "6") (pinfunction "D1_6") (pintype "bidirectional"))
      (node (ref "R12") (pin "2") (pinfunction "2_2") (pintype "passive"))
      (node (ref "RST") (pin "X") (pinfunction "P$1_X") (pintype "passive"))
      (node (ref "U3") (pin "19") (pinfunction "RESET_N_19") (pintype "bidirectional"))
    )
    (net (code "29") (name "Net-(Q1-G2)") (class "Default")
      (node (ref "Q1") (pin "5") (pinfunction "G2_5") (pintype "bidirectional"))
      (node (ref "R10") (pin "2") (pinfunction "2_2") (pintype "passive"))
      (node (ref "R11") (pin "2") (pinfunction "2_2") (pintype "passive"))
    )
    (net (code "30") (name "Net-(U1-PA00(XIN32{slash}SER1:0{slash}TC2:0))") (class "Default")
      (node (ref "C2") (pin "2") (pinfunction "2_2") (pintype "passive"))
      (node (ref "U1") (pin "1") (pinfunction "PA00(XIN32/SER1:0/TC2:0)_1") (pintype "bidirectional"))
      (node (ref "Y1") (pin "2") (pinfunction "2_2") (pintype "passive"))
    )
    (net (code "31") (name "Net-(U1-PA01(XOUT32{slash}SER1:1{slash}TC2:1))") (class "Default")
      (node (ref "C3") (pin "2") (pinfunction "2_2") (pintype "passive"))
      (node (ref "U1") (pin "2") (pinfunction "PA01(XOUT32/SER1:1/TC2:1)_2") (pintype "bidirectional"))
      (node (ref "Y1") (pin "1") (pinfunction "1_1") (pintype "passive"))
    )
    (net (code "32") (name "Net-(U1-PA04(AIN4{slash}REFB{slash}SER0:0{slash}TC0:0))") (class "Default")
      (node (ref "D1") (pin "A") (pinfunction "A_A") (pintype "passive"))
      (node (ref "U1") (pin "9") (pinfunction "PA04(AIN4/REFB/SER0:0/TC0:0)_9") (pintype "bidirectional"))
    )
    (net (code "33") (name "Net-(U1-VDDANA)") (class "Default")
      (node (ref "C4") (pin "2") (pinfunction "2_2") (pintype "passive"))
      (node (ref "C5") (pin "2") (pinfunction "2_2") (pintype "passive"))
      (node (ref "L3") (pin "2") (pinfunction "2_2") (pintype "passive"))
      (node (ref "U1") (pin "6") (pinfunction "VDDANA_6") (pintype "bidirectional"))
    )
    (net (code "34") (name "Net-(U1-VDDCORE)") (class "Default")
      (node (ref "C9") (pin "2") (pinfunction "2_2") (pintype "passive"))
      (node (ref "U1") (pin "43") (pinfunction "VDDCORE_43") (pintype "bidirectional"))
    )
    (net (code "35") (name "Net-(U3-GPIO_8{slash}_RMII_TXEN{slash}_SPI_V_HD{slash})") (class "Default")
      (node (ref "R13") (pin "2") (pinfunction "2_2") (pintype "passive"))
      (node (ref "U3") (pin "8") (pinfunction "GPIO_8/_RMII_TXEN/_SPI_V_HD/_8") (pintype "bidirectional"))
    )
    (net (code "36") (name "Net-(U3-GPIO_24{slash}_RMII_MDIO)") (class "Default")
      (node (ref "R10") (pin "1") (pinfunction "1_1") (pintype "passive"))
      (node (ref "U3") (pin "24") (pinfunction "GPIO_24/_RMII_MDIO_24") (pintype "bidirectional"))
    )
    (net (code "37") (name "Net-(U5-PROG)") (class "Default")
      (node (ref "R22") (pin "1") (pinfunction "1_1") (pintype "passive"))
      (node (ref "U5") (pin "5") (pinfunction "PROG_5") (pintype "bidirectional"))
    )
    (net (code "38") (name "Net-(U5-STAT)") (class "Default")
      (node (ref "R20") (pin "2") (pinfunction "2_2") (pintype "passive"))
      (node (ref "R21") (pin "2") (pinfunction "2_2") (pintype "passive"))
      (node (ref "U5") (pin "1") (pinfunction "STAT_1") (pintype "bidirectional"))
    )
    (net (code "39") (name "Net-(U6-CAP+)") (class "Default")
      (node (ref "C20") (pin "1") (pinfunction "1_1") (pintype "passive"))
      (node (ref "U6") (pin "6") (pinfunction "CAP+_6") (pintype "power_in"))
    )
    (net (code "40") (name "Net-(U6-CAP-)") (class "Default")
      (node (ref "C20") (pin "2") (pinfunction "2_2") (pintype "passive"))
      (node (ref "U6") (pin "3") (pinfunction "CAP-_3") (pintype "power_in"))
    )
    (net (code "41") (name "Net-(U7-NR)") (class "Default")
      (node (ref "C25") (pin "2") (pinfunction "2_2") (pintype "passive"))
      (node (ref "U7") (pin "4") (pinfunction "NR_4") (pintype "bidirectional"))
    )
    (net (code "42") (name "Net-(U9-PG)") (class "Default")
      (node (ref "R25") (pin "2") (pinfunction "2_2") (pintype "passive"))
      (node (ref "U9") (pin "3") (pinfunction "PG_3") (pintype "output"))
    )
    (net (code "43") (name "Net-(U17-CPOUT)") (class "Default")
      (node (ref "C37") (pin "2") (pinfunction "2_2") (pintype "passive"))
      (node (ref "U17") (pin "20") (pinfunction "CPOUT_20") (pintype "bidirectional"))
    )
    (net (code "44") (name "Net-(U17-REGOUT)") (class "Default")
      (node (ref "C35") (pin "2") (pinfunction "2_2") (pintype "passive"))
      (node (ref "U17") (pin "10") (pinfunction "REGOUT_10") (pintype "bidirectional"))
    )
    (net (code "45") (name "Net-(U18-PG)") (class "Default")
      (node (ref "R27") (pin "2") (pinfunction "2_2") (pintype "passive"))
      (node (ref "U18") (pin "3") (pinfunction "PG_3") (pintype "output"))
    )
    (net (code "46") (name "PA02_EDA_SIG") (class "Default")
      (node (ref "J1") (pin "2") (pinfunction "2_2") (pintype "passive"))
      (node (ref "U1") (pin "3") (pinfunction "PA02(AIN0/DAC)_3") (pintype "bidirectional"))
    )
    (net (code "47") (name "PA07_DRDY") (class "Default")
      (node (ref "J1") (pin "18") (pinfunction "18_18") (pintype "passive"))
      (node (ref "U1") (pin "12") (pinfunction "PA07(AIN7/SER0:3/TC1:1)_12") (pintype "bidirectional"))
    )
    (net (code "48") (name "PA10_D2") (class "Default")
      (node (ref "U1") (pin "15") (pinfunction "PA10(AIN18/SER0:2+)_15") (pintype "bidirectional"))
    )
    (net (code "49") (name "PA12_S2_TX_MOSI") (class "Default")
      (node (ref "U1") (pin "21") (pinfunction "PA12(I2C/SER2:0+)_21") (pintype "bidirectional"))
      (node (ref "U3") (pin "36") (pinfunction "GPIO_36/_JTAG_TDI/_36") (pintype "bidirectional"))
    )
    (net (code "50") (name "PA13_S2_RX_MISO") (class "Default")
      (node (ref "U1") (pin "22") (pinfunction "PA13(I2C/SER2:1+)_22") (pintype "bidirectional"))
      (node (ref "U3") (pin "1") (pinfunction "GPIO_1/_SPI_V_DI_1") (pintype "bidirectional"))
    )
    (net (code "51") (name "PA14_S2_RTS_CS") (class "Default")
      (node (ref "U1") (pin "23") (pinfunction "PA14(XIN/SER2:2+)_23") (pintype "bidirectional"))
      (node (ref "U3") (pin "21") (pinfunction "GPIO_21/_UART_CTS/_RMII_TXD0/_SPI_V_DO/_21") (pintype "bidirectional"))
      (node (ref "U3") (pin "28") (pinfunction "GPIO_28/_SPI_V_CS_28") (pintype "bidirectional"))
    )
    (net (code "52") (name "PA15_S2_CTS_SCK") (class "Default")
      (node (ref "U1") (pin "24") (pinfunction "PA15(XOUT/SER2:3+)_24") (pintype "bidirectional"))
      (node (ref "U3") (pin "20") (pinfunction "GPIO_20/_UART_RTS/_RMII_TXD1/_SPI_V_WP_20") (pintype "bidirectional"))
      (node (ref "U3") (pin "29") (pinfunction "GPIO_29/_SPI_V_CLK_29") (pintype "bidirectional"))
    )
    (net (code "53") (name "PA16_S1_MOSI") (class "Default")
      (node (ref "J1") (pin "24") (pinfunction "24_24") (pintype "passive"))
      (node (ref "MOSI") (pin "X") (pinfunction "P$1_X") (pintype "passive"))
      (node (ref "U1") (pin "25") (pinfunction "PA16(I2C/SER1:0+)_25") (pintype "bidirectional"))
    )
    (net (code "54") (name "PA17_S1_SCK") (class "Default")
      (node (ref "J1") (pin "20") (pinfunction "20_20") (pintype "passive"))
      (node (ref "SCK") (pin "X") (pinfunction "P$1_X") (pintype "passive"))
      (node (ref "U1") (pin "26") (pinfunction "PA17(I2C/SER1:1+)_26") (pintype "bidirectional"))
    )
    (net (code "55") (name "PA18_OTG") (class "Default")
      (node (ref "J3") (pin "4") (pinfunction "4_4") (pintype "passive"))
      (node (ref "U1") (pin "27") (pinfunction "PA18(SER1:2+)_27") (pintype "bidirectional"))
    )
    (net (code "56") (name "PA19_S1_MISO") (class "Default")
      (node (ref "J1") (pin "19") (pinfunction "19_19") (pintype "passive"))
      (node (ref "MISO") (pin "X") (pinfunction "P$1_X") (pintype "passive"))
      (node (ref "U1") (pin "28") (pinfunction "PA19(SER1:3+)_28") (pintype "bidirectional"))
    )
    (net (code "57") (name "PA20_CS") (class "Default")
      (node (ref "CS") (pin "X") (pinfunction "P$1_X") (pintype "passive"))
      (node (ref "J1") (pin "21") (pinfunction "21_21") (pintype "passive"))
      (node (ref "U1") (pin "29") (pinfunction "PA20(SER5:2+)_29") (pintype "bidirectional"))
    )
    (net (code "58") (name "PA27_GPIO0") (class "Default")
      (node (ref "GPIO0") (pin "X") (pinfunction "P$1_X") (pintype "passive"))
      (node (ref "U1") (pin "39") (pinfunction "PA27_39") (pintype "bidirectional"))
      (node (ref "U3") (pin "27") (pinfunction "GPIO_27/_RMII_CLK/_SYS_BOOT_27") (pintype "bidirectional"))
    )
    (net (code "59") (name "PA28_ACK") (class "Default")
      (node (ref "U1") (pin "41") (pinfunction "PA28_41") (pintype "bidirectional"))
      (node (ref "U3") (pin "7") (pinfunction "GPIO_7_7") (pintype "bidirectional"))
    )
    (net (code "60") (name "PA30_SWCLK") (class "Default")
      (node (ref "J8") (pin "4") (pinfunction "4_4") (pintype "bidirectional"))
      (node (ref "R13") (pin "1") (pinfunction "1_1") (pintype "passive"))
      (node (ref "R4") (pin "1") (pinfunction "1_1") (pintype "passive"))
      (node (ref "U1") (pin "45") (pinfunction "PA30(SWCLK/SER1:2+)_45") (pintype "bidirectional"))
    )
    (net (code "61") (name "PA31_SWDIO") (class "Default")
      (node (ref "J8") (pin "2") (pinfunction "2_2") (pintype "bidirectional"))
      (node (ref "R19") (pin "1") (pinfunction "1_1") (pintype "passive"))
      (node (ref "U1") (pin "46") (pinfunction "PA31(SWDIO/SER1:3+)_46") (pintype "bidirectional"))
    )
    (net (code "62") (name "PB08_RST") (class "Default")
      (node (ref "Q1") (pin "2") (pinfunction "G1_2") (pintype "bidirectional"))
      (node (ref "R9") (pin "2") (pinfunction "2_2") (pintype "passive"))
      (node (ref "U1") (pin "7") (pinfunction "PB08(AIN2/SER4:0/TC4:0)_7") (pintype "bidirectional"))
    )
    (net (code "63") (name "PB11_CLKSEL") (class "Default")
      (node (ref "U1") (pin "20") (pinfunction "PB11(SER4:3+)_20") (pintype "bidirectional"))
    )
    (net (code "64") (name "PB22_S5_TX") (class "Default")
      (node (ref "RX") (pin "X") (pinfunction "P$1_X") (pintype "passive"))
      (node (ref "U1") (pin "37") (pinfunction "PB22(SER5:2+)_37") (pintype "bidirectional"))
      (node (ref "U3") (pin "23") (pinfunction "GPIO_23/_UART_RXD_23") (pintype "bidirectional"))
    )
    (net (code "65") (name "PB23_S5_RX") (class "Default")
      (node (ref "TX") (pin "X") (pinfunction "P$1_X") (pintype "passive"))
      (node (ref "U1") (pin "38") (pinfunction "PB23(SER5:3+)_38") (pintype "bidirectional"))
      (node (ref "U3") (pin "22") (pinfunction "GPIO_22/_UART_TXD_22") (pintype "bidirectional"))
    )
    (net (code "66") (name "RED") (class "Default")
      (node (ref "D3") (pin "A2") (pinfunction "A2_A2") (pintype "bidirectional"))
      (node (ref "U3") (pin "17") (pinfunction "GPIO_17/_RMII_RXD1/_DAC_17_17") (pintype "bidirectional"))
    )
    (net (code "67") (name "RESET#") (class "Default")
      (node (ref "Q1") (pin "3") (pinfunction "D2_3") (pintype "bidirectional"))
      (node (ref "R5") (pin "2") (pinfunction "2_2") (pintype "passive"))
    )
    (net (code "68") (name "RESETN") (class "Default")
      (node (ref "C1") (pin "1") (pinfunction "1_1") (pintype "passive"))
      (node (ref "R2") (pin "1") (pinfunction "1_1") (pintype "passive"))
      (node (ref "R3") (pin "1") (pinfunction "1_1") (pintype "passive"))
      (node (ref "R5") (pin "1") (pinfunction "1_1") (pintype "passive"))
      (node (ref "R6") (pin "2") (pinfunction "2_2") (pintype "passive"))
      (node (ref "U1") (pin "40") (pinfunction "~{RESET}_40") (pintype "bidirectional"))
    )
    (net (code "69") (name "S0_I2C_SCL") (class "Default")
      (node (ref "J1") (pin "16") (pinfunction "16_16") (pintype "passive"))
      (node (ref "R14") (pin "2") (pinfunction "2_2") (pintype "passive"))
      (node (ref "R8") (pin "1") (pinfunction "1_1") (pintype "passive"))
      (node (ref "U1") (pin "14") (pinfunction "PA09(I2C/AIN17/SER0:1+)_14") (pintype "bidirectional"))
      (node (ref "U17") (pin "23") (pinfunction "SCL_23") (pintype "bidirectional"))
      (node (ref "U4") (pin "6") (pinfunction "SCL_6") (pintype "bidirectional"))
    )
    (net (code "70") (name "S0_I2C_SDA") (class "Default")
      (node (ref "J1") (pin "17") (pinfunction "17_17") (pintype "passive"))
      (node (ref "R18") (pin "2") (pinfunction "2_2") (pintype "passive"))
      (node (ref "R7") (pin "1") (pinfunction "1_1") (pintype "passive"))
      (node (ref "U1") (pin "13") (pinfunction "PA08(I2C/AIN16/SER0:0+)_13") (pintype "bidirectional"))
      (node (ref "U17") (pin "24") (pinfunction "SDA_24") (pintype "bidirectional"))
      (node (ref "U4") (pin "5") (pinfunction "SDA_5") (pintype "bidirectional"))
    )
    (net (code "71") (name "USBN") (class "Default")
      (node (ref "D-1") (pin "X") (pinfunction "P$1_X") (pintype "passive"))
      (node (ref "D2") (pin "3") (pinfunction "3_3") (pintype "passive"))
      (node (ref "J3") (pin "2") (pinfunction "2_2") (pintype "passive"))
      (node (ref "U1") (pin "33") (pinfunction "PA24(SER3:2+)_33") (pintype "bidirectional"))
    )
    (net (code "72") (name "USBP") (class "Default")
      (node (ref "D+1") (pin "X") (pinfunction "P$1_X") (pintype "passive"))
      (node (ref "D2") (pin "2") (pinfunction "2_2") (pintype "passive"))
      (node (ref "J3") (pin "3") (pinfunction "3_3") (pintype "passive"))
      (node (ref "U1") (pin "34") (pinfunction "PA25(SER3:3+)_34") (pintype "bidirectional"))
    )
    (net (code "73") (name "VBAT_LVL") (class "Default")
      (node (ref "C33") (pin "2") (pinfunction "2_2") (pintype "passive"))
      (node (ref "R23") (pin "1") (pinfunction "1_1") (pintype "passive"))
      (node (ref "R24") (pin "2") (pinfunction "2_2") (pintype "passive"))
      (node (ref "U1") (pin "10") (pinfunction "PA05(AIN5/SER0:1/TC0:1)_10") (pintype "bidirectional"))
    )
    (net (code "74") (name "VCC") (class "Default")
      (node (ref "C10") (pin "2") (pinfunction "2_2") (pintype "passive"))
      (node (ref "C11") (pin "2") (pinfunction "2_2") (pintype "passive"))
      (node (ref "C12") (pin "1") (pinfunction "1_1") (pintype "passive"))
      (node (ref "C13") (pin "2") (pinfunction "2_2") (pintype "passive"))
      (node (ref "C14") (pin "2") (pinfunction "2_2") (pintype "passive"))
      (node (ref "C18") (pin "2") (pinfunction "2_2") (pintype "passive"))
      (node (ref "C28") (pin "2") (pinfunction "2_2") (pintype "passive"))
      (node (ref "C29") (pin "1") (pinfunction "1_1") (pintype "passive"))
      (node (ref "C30") (pin "2") (pinfunction "2_2") (pintype "passive"))
      (node (ref "C31") (pin "1") (pinfunction "1_1") (pintype "passive"))
      (node (ref "C34") (pin "2") (pinfunction "2_2") (pintype "passive"))
      (node (ref "C36") (pin "2") (pinfunction "2_2") (pintype "passive"))
      (node (ref "C53") (pin "1") (pinfunction "1_1") (pintype "passive"))
      (node (ref "C8") (pin "2") (pinfunction "2_2") (pintype "passive"))
      (node (ref "J1") (pin "11") (pinfunction "11_11") (pintype "passive"))
      (node (ref "J1") (pin "12") (pinfunction "12_12") (pintype "passive"))
      (node (ref "J8") (pin "1") (pinfunction "1_1") (pintype "bidirectional"))
      (node (ref "L3") (pin "1") (pinfunction "1_1") (pintype "passive"))
      (node (ref "R12") (pin "1") (pinfunction "1_1") (pintype "passive"))
      (node (ref "R27") (pin "1") (pinfunction "1_1") (pintype "passive"))
      (node (ref "R3") (pin "2") (pinfunction "2_2") (pintype "passive"))
      (node (ref "R4") (pin "2") (pinfunction "2_2") (pintype "passive"))
      (node (ref "R7") (pin "2") (pinfunction "2_2") (pintype "passive"))
      (node (ref "R8") (pin "2") (pinfunction "2_2") (pintype "passive"))
      (node (ref "U1") (pin "17") (pinfunction "VDDIO_17") (pintype "bidirectional"))
      (node (ref "U1") (pin "36") (pinfunction "VDDIO_36") (pintype "bidirectional"))
      (node (ref "U1") (pin "44") (pinfunction "VDDIN_44") (pintype "bidirectional"))
      (node (ref "U17") (pin "13") (pinfunction "VDD_13") (pintype "bidirectional"))
      (node (ref "U17") (pin "8") (pinfunction "VLOGIC_8") (pintype "bidirectional"))
      (node (ref "U18") (pin "1") (pinfunction "OUT_1") (pintype "power_in"))
      (node (ref "U3") (pin "10") (pinfunction "VCC_10") (pintype "bidirectional"))
      (node (ref "U3") (pin "9") (pinfunction "VCC_IO_9") (pintype "bidirectional"))
      (node (ref "U4") (pin "8") (pinfunction "VCC_8") (pintype "bidirectional"))
    )
    (net (code "75") (name "V_BATT") (class "Default")
      (node (ref "C19") (pin "2") (pinfunction "2_2") (pintype "passive"))
      (node (ref "C7") (pin "2") (pinfunction "2_2") (pintype "passive"))
      (node (ref "R23") (pin "2") (pinfunction "2_2") (pintype "passive"))
      (node (ref "S1") (pin "3") (pinfunction "3_3") (pintype "bidirectional"))
      (node (ref "S1") (pin "6") (pinfunction "6_6") (pintype "bidirectional"))
      (node (ref "U18") (pin "4") (pinfunction "EN_4") (pintype "input"))
      (node (ref "U18") (pin "6") (pinfunction "IN_6") (pintype "power_in"))
      (node (ref "U9") (pin "4") (pinfunction "EN_4") (pintype "input"))
      (node (ref "U9") (pin "6") (pinfunction "IN_6") (pintype "power_in"))
    )
    (net (code "76") (name "_V_BATT") (class "Default")
      (node (ref "C17") (pin "1") (pinfunction "+_1") (pintype "bidirectional"))
      (node (ref "J6") (pin "1") (pinfunction "2_1") (pintype "passive"))
      (node (ref "S1") (pin "2") (pinfunction "2_2") (pintype "bidirectional"))
      (node (ref "S1") (pin "5") (pinfunction "5_5") (pintype "bidirectional"))
      (node (ref "U5") (pin "3") (pinfunction "VBAT_3") (pintype "bidirectional"))
    )
    (net (code "77") (name "unconnected-(J1-Pad1)") (class "Default")
      (node (ref "J1") (pin "1") (pinfunction "1_1") (pintype "passive"))
    )
    (net (code "78") (name "unconnected-(J1-PadMP1)") (class "Default")
      (node (ref "J1") (pin "MP1") (pinfunction "MP1_MP1") (pintype "passive"))
    )
    (net (code "79") (name "unconnected-(J1-PadMP2)") (class "Default")
      (node (ref "J1") (pin "MP2") (pinfunction "MP2_MP2") (pintype "passive"))
    )
    (net (code "80") (name "unconnected-(J8-Pad6)") (class "Default")
      (node (ref "J8") (pin "6") (pinfunction "6_6") (pintype "bidirectional"))
    )
    (net (code "81") (name "unconnected-(S1-Pad1)") (class "Default")
      (node (ref "S1") (pin "1") (pinfunction "1_1") (pintype "bidirectional"))
    )
    (net (code "82") (name "unconnected-(S1-Pad4)") (class "Default")
      (node (ref "S1") (pin "4") (pinfunction "4_4") (pintype "bidirectional"))
    )
    (net (code "83") (name "unconnected-(U1-PA03(AIN1{slash}REFA)-Pad4)") (class "Default")
      (node (ref "U1") (pin "4") (pinfunction "PA03(AIN1/REFA)_4") (pintype "bidirectional"))
    )
    (net (code "84") (name "unconnected-(U1-PA11(AIN19{slash}SER0:3+)-Pad16)") (class "Default")
      (node (ref "U1") (pin "16") (pinfunction "PA11(AIN19/SER0:3+)_16") (pintype "bidirectional"))
    )
    (net (code "85") (name "unconnected-(U1-PA21(SER5:3+)-Pad30)") (class "Default")
      (node (ref "U1") (pin "30") (pinfunction "PA21(SER5:3+)_30") (pintype "bidirectional"))
    )
    (net (code "86") (name "unconnected-(U1-PA22(I2C{slash}SER3:0+)-Pad31)") (class "Default")
      (node (ref "U1") (pin "31") (pinfunction "PA22(I2C/SER3:0+)_31") (pintype "bidirectional"))
    )
    (net (code "87") (name "unconnected-(U1-PB02(AIN10{slash}SER5:0)-Pad47)") (class "Default")
      (node (ref "U1") (pin "47") (pinfunction "PB02(AIN10/SER5:0)_47") (pintype "bidirectional"))
    )
    (net (code "88") (name "unconnected-(U1-PB10(SER4:2+)-Pad19)") (class "Default")
      (node (ref "U1") (pin "19") (pinfunction "PB10(SER4:2+)_19") (pintype "bidirectional"))
    )
    (net (code "89") (name "unconnected-(U3-ANT-Pad13)") (class "Default")
      (node (ref "U3") (pin "13") (pinfunction "ANT_13") (pintype "bidirectional"))
    )
    (net (code "90") (name "unconnected-(U3-GPIO_25{slash}_RMII_MDCLK{slash}-Pad25)") (class "Default")
      (node (ref "U3") (pin "25") (pinfunction "GPIO_25/_RMII_MDCLK/_25") (pintype "bidirectional"))
    )
    (net (code "91") (name "unconnected-(U3-GPI_2{slash}_ADC_2-Pad2)") (class "Default")
      (node (ref "U3") (pin "2") (pinfunction "GPI_2/_ADC_2_2") (pintype "bidirectional"))
    )
    (net (code "92") (name "unconnected-(U3-GPI_3{slash}_ADC_3-Pad3)") (class "Default")
      (node (ref "U3") (pin "3") (pinfunction "GPI_3/_ADC_3_3") (pintype "bidirectional"))
    )
    (net (code "93") (name "unconnected-(U3-GPI_4{slash}_ADC_4-Pad4)") (class "Default")
      (node (ref "U3") (pin "4") (pinfunction "GPI_4/_ADC_4_4") (pintype "bidirectional"))
    )
    (net (code "94") (name "unconnected-(U3-GPI_34{slash}_ADC_3-Pad34)") (class "Default")
      (node (ref "U3") (pin "34") (pinfunction "GPI_34/_ADC_3_34") (pintype "bidirectional"))
    )
    (net (code "95") (name "unconnected-(U3-RSVD_1-Pad11)") (class "Default")
      (node (ref "U3") (pin "11") (pinfunction "RSVD_1_11") (pintype "bidirectional"))
    )
    (net (code "96") (name "unconnected-(U3-RSVD_2-Pad15)") (class "Default")
      (node (ref "U3") (pin "15") (pinfunction "RSVD_2_15") (pintype "bidirectional"))
    )
    (net (code "97") (name "unconnected-(U3-RSVD_3-Pad33)") (class "Default")
      (node (ref "U3") (pin "33") (pinfunction "RSVD_3_33") (pintype "bidirectional"))
    )
    (net (code "98") (name "unconnected-(U4-EP-Pad9)") (class "Default")
      (node (ref "U4") (pin "9") (pinfunction "EP_9") (pintype "bidirectional"))
    )
    (net (code "99") (name "unconnected-(U4-NC_1-Pad1)") (class "Default")
      (node (ref "U4") (pin "1") (pinfunction "NC_1_1") (pintype "bidirectional"))
    )
    (net (code "100") (name "unconnected-(U4-NC_2-Pad2)") (class "Default")
      (node (ref "U4") (pin "2") (pinfunction "NC_2_2") (pintype "bidirectional"))
    )
    (net (code "101") (name "unconnected-(U4-NC_3-Pad3)") (class "Default")
      (node (ref "U4") (pin "3") (pinfunction "NC_3_3") (pintype "bidirectional"))
    )
    (net (code "102") (name "unconnected-(U4-NC_4-Pad7)") (class "Default")
      (node (ref "U4") (pin "7") (pinfunction "NC_4_7") (pintype "bidirectional"))
    )
    (net (code "103") (name "unconnected-(U8-NC-Pad4)") (class "Default")
      (node (ref "U8") (pin "4") (pinfunction "NC_4") (pintype "no_connect"))
    )
    (net (code "104") (name "unconnected-(U17-AUX_CL-Pad7)") (class "Default")
      (node (ref "U17") (pin "7") (pinfunction "AUX_CL_7") (pintype "bidirectional"))
    )
    (net (code "105") (name "unconnected-(U17-AUX_DA-Pad6)") (class "Default")
      (node (ref "U17") (pin "6") (pinfunction "AUX_DA_6") (pintype "bidirectional"))
    )
    (net (code "106") (name "unconnected-(U17-EP-Pad25)") (class "Default")
      (node (ref "U17") (pin "25") (pinfunction "EP_25") (pintype "bidirectional"))
    )
    (net (code "107") (name "unconnected-(U17-NC_1-Pad2)") (class "Default")
      (node (ref "U17") (pin "2") (pinfunction "NC_1_2") (pintype "bidirectional"))
    )
    (net (code "108") (name "unconnected-(U17-NC_2-Pad3)") (class "Default")
      (node (ref "U17") (pin "3") (pinfunction "NC_2_3") (pintype "bidirectional"))
    )
    (net (code "109") (name "unconnected-(U17-NC_3-Pad4)") (class "Default")
      (node (ref "U17") (pin "4") (pinfunction "NC_3_4") (pintype "bidirectional"))
    )
    (net (code "110") (name "unconnected-(U17-NC_4-Pad5)") (class "Default")
      (node (ref "U17") (pin "5") (pinfunction "NC_4_5") (pintype "bidirectional"))
    )
    (net (code "111") (name "unconnected-(U17-NC_5-Pad14)") (class "Default")
      (node (ref "U17") (pin "14") (pinfunction "NC_5_14") (pintype "bidirectional"))
    )
    (net (code "112") (name "unconnected-(U17-NC_6-Pad15)") (class "Default")
      (node (ref "U17") (pin "15") (pinfunction "NC_6_15") (pintype "bidirectional"))
    )
    (net (code "113") (name "unconnected-(U17-NC_7-Pad16)") (class "Default")
      (node (ref "U17") (pin "16") (pinfunction "NC_7_16") (pintype "bidirectional"))
    )
    (net (code "114") (name "unconnected-(U17-NC_8-Pad17)") (class "Default")
      (node (ref "U17") (pin "17") (pinfunction "NC_8_17") (pintype "bidirectional"))
    )
    (net (code "115") (name "unconnected-(U17-RESV_1-Pad19)") (class "Default")
      (node (ref "U17") (pin "19") (pinfunction "RESV_1_19") (pintype "bidirectional"))
    )
    (net (code "116") (name "unconnected-(U17-RESV_2-Pad21)") (class "Default")
      (node (ref "U17") (pin "21") (pinfunction "RESV_2_21") (pintype "bidirectional"))
    )
    (net (code "117") (name "unconnected-(U17-RESV_3-Pad22)") (class "Default")
      (node (ref "U17") (pin "22") (pinfunction "RESV_3_22") (pintype "bidirectional"))
    )
  )
)
